# eth_lan8742a_phy.net
KiCad netlist of a schematic drawn in Altium Designer
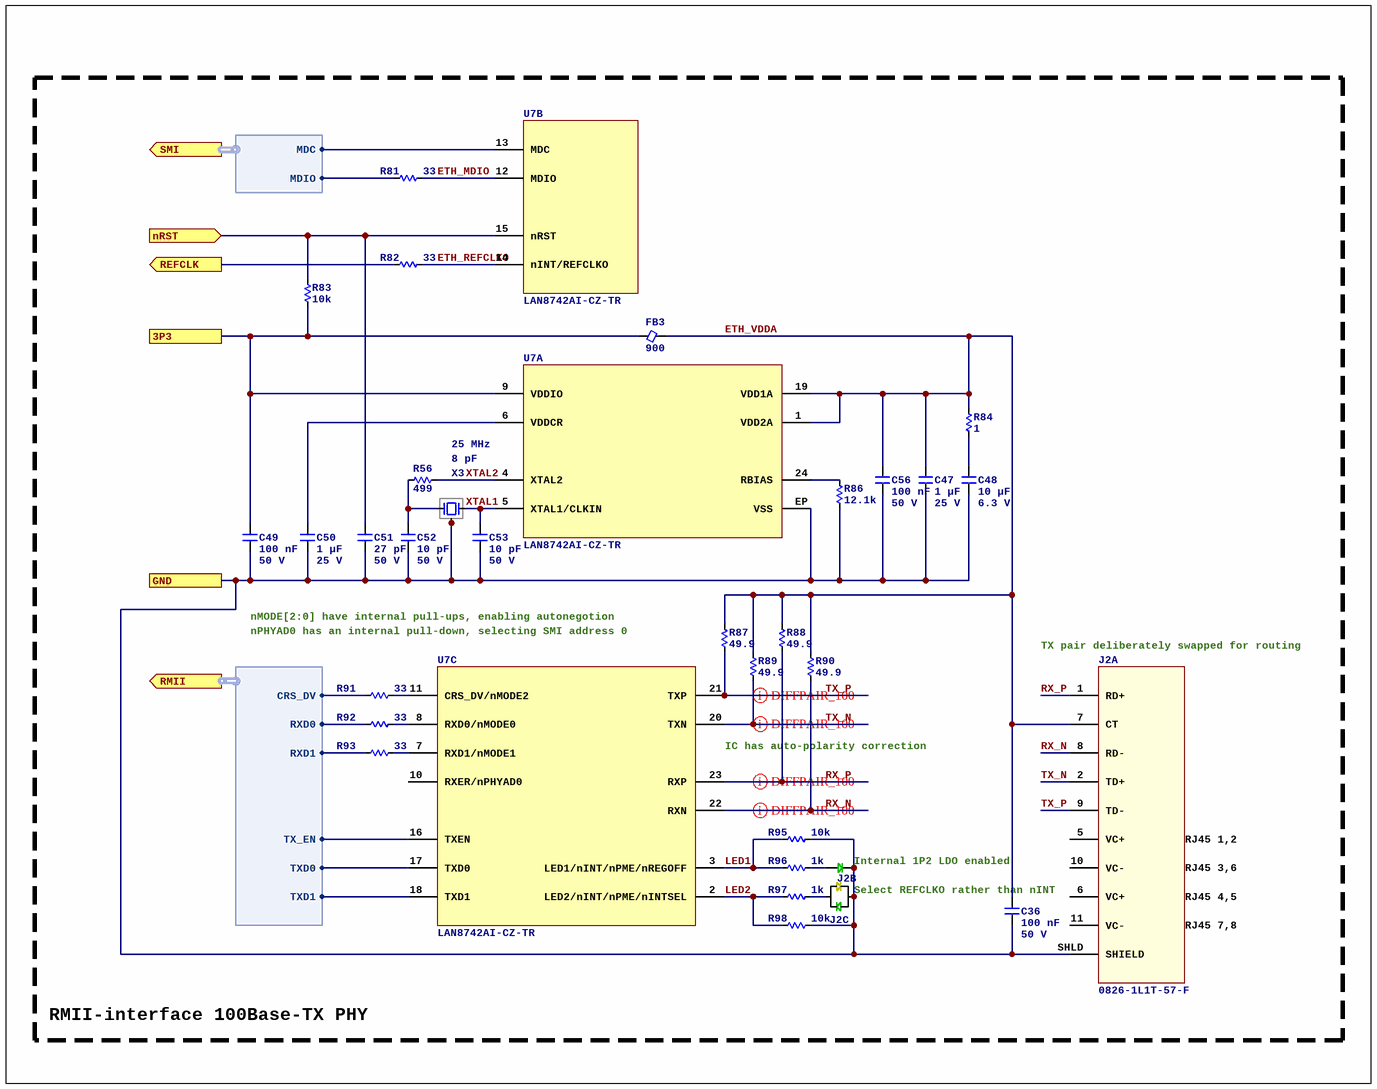
[diagram p0: eth_lan8742a_phy.SchDoc]

(export (version "E")
  (design (tool "Eeschema 10.0.6"))
  (components
    (comp (ref "C36")
      (value "CL05B104KB54PNC")
      (footprint "C0402")
      (fields
        (field (name "CAPACITANCE") "100 nF")
        (field (name "MANUFACTURER") "Samsung Electro-Mechanics")
        (field (name "VOLTAGE RATING") "50 V")
      )
      (libsource (lib "database") (part "__template_cap"))
    )
    (comp (ref "C47")
      (value "CL10B105KA8NNNC")
      (footprint "C0603")
      (fields
        (field (name "CAPACITANCE") "1 µF")
        (field (name "MANUFACTURER") "Samsung Electro-Mechanics")
        (field (name "VOLTAGE RATING") "25 V")
      )
      (libsource (lib "database") (part "__template_cap"))
    )
    (comp (ref "C48")
      (value "CC0805KKX7R5BB106")
      (footprint "C0805")
      (fields
        (field (name "CAPACITANCE") "10 µF")
        (field (name "MANUFACTURER") "YAGEO")
        (field (name "VOLTAGE RATING") "6.3 V")
      )
      (libsource (lib "database") (part "__template_cap"))
    )
    (comp (ref "C49")
      (value "CL05B104KB54PNC")
      (footprint "C0402")
      (fields
        (field (name "CAPACITANCE") "100 nF")
        (field (name "MANUFACTURER") "Samsung Electro-Mechanics")
        (field (name "VOLTAGE RATING") "50 V")
      )
      (libsource (lib "database") (part "__template_cap"))
    )
    (comp (ref "C50")
      (value "CL10B105KA8NNNC")
      (footprint "C0603")
      (fields
        (field (name "CAPACITANCE") "1 µF")
        (field (name "MANUFACTURER") "Samsung Electro-Mechanics")
        (field (name "VOLTAGE RATING") "25 V")
      )
      (libsource (lib "database") (part "__template_cap"))
    )
    (comp (ref "C51")
      (value "CC0402JRNPO9BN270")
      (footprint "C0402")
      (fields
        (field (name "CAPACITANCE") "27 pF")
        (field (name "MANUFACTURER") "YAGEO")
        (field (name "VOLTAGE RATING") "50 V")
      )
      (libsource (lib "database") (part "__template_cap"))
    )
    (comp (ref "C52")
      (value "CL05C100JB5NNNC")
      (footprint "C0402")
      (fields
        (field (name "CAPACITANCE") "10 pF")
        (field (name "MANUFACTURER") "Samsung Electro-Mechanics")
        (field (name "VOLTAGE RATING") "50 V")
      )
      (libsource (lib "database") (part "__template_cap"))
    )
    (comp (ref "C53")
      (value "CL05C100JB5NNNC")
      (footprint "C0402")
      (fields
        (field (name "CAPACITANCE") "10 pF")
        (field (name "MANUFACTURER") "Samsung Electro-Mechanics")
        (field (name "VOLTAGE RATING") "50 V")
      )
      (libsource (lib "database") (part "__template_cap"))
    )
    (comp (ref "C56")
      (value "CL05B104KB54PNC")
      (footprint "C0402")
      (fields
        (field (name "CAPACITANCE") "100 nF")
        (field (name "MANUFACTURER") "Samsung Electro-Mechanics")
        (field (name "VOLTAGE RATING") "50 V")
      )
      (libsource (lib "database") (part "__template_cap"))
    )
    (comp (ref "FB3")
      (value "BLM15PX601SN1D")
      (footprint "FB0402")
      (fields (field (name "MANUFACTURER") "Murata Electronics") (field (name "CURRENT RATING (MA)") "900"))
      (libsource (lib "database") (part "__template_fb"))
    )
    (comp (ref "J2")
      (value "0826-1L1T-57-F")
      (footprint "BELFUSE_0826-1L1T-57-F")
      (description "CONN MAGJACK 1PORT 100 BASE-T")
      (fields (field (name "MANUFACTURER") "Bel Fuse Inc"))
      (libsource (lib "") (part "0826-1L1T-57-F_2"))
    )
    (comp (ref "R56")
      (value "499")
      (footprint "R0402")
      (fields
        (field (name "TOLERANCE") "1%")
        (field (name "MANUFACTURER PART NUMBER") "0402WGF4990TCE")
        (field (name "MANUFACTURER") "UNI-ROYAL(Uniroyal Elec)")
      )
      (libsource (lib "database") (part "__template_resistor"))
    )
    (comp (ref "R81")
      (value "33")
      (footprint "R0402")
      (fields
        (field (name "TOLERANCE") "1%")
        (field (name "MANUFACTURER PART NUMBER") "CRCW040233R0FKED")
        (field (name "MANUFACTURER") "Vishay Intertech")
      )
      (libsource (lib "database") (part "__template_resistor"))
    )
    (comp (ref "R82")
      (value "33")
      (footprint "R0402")
      (fields
        (field (name "TOLERANCE") "1%")
        (field (name "MANUFACTURER PART NUMBER") "CRCW040233R0FKED")
        (field (name "MANUFACTURER") "Vishay Intertech")
      )
      (libsource (lib "database") (part "__template_resistor"))
    )
    (comp (ref "R83")
      (value "10k")
      (footprint "R0402")
      (fields
        (field (name "TOLERANCE") "1%")
        (field (name "MANUFACTURER PART NUMBER") "0402WGF1002TCE")
        (field (name "MANUFACTURER") "UNI-ROYAL(Uniroyal Elec)")
      )
      (libsource (lib "database") (part "__template_resistor"))
    )
    (comp (ref "R84")
      (value "1")
      (footprint "R0402")
      (fields
        (field (name "TOLERANCE") "1%")
        (field (name "MANUFACTURER PART NUMBER") "CRCW04021R00FKEDC")
        (field (name "MANUFACTURER") "Vishay Intertech")
      )
      (libsource (lib "database") (part "__template_resistor"))
    )
    (comp (ref "R86")
      (value "12.1k")
      (footprint "R0402")
      (fields
        (field (name "TOLERANCE") "1%")
        (field (name "MANUFACTURER PART NUMBER") "RC0402FR-0712K1L")
        (field (name "MANUFACTURER") "YAGEO")
      )
      (libsource (lib "database") (part "__template_resistor"))
    )
    (comp (ref "R87")
      (value "49.9")
      (footprint "R0402")
      (fields
        (field (name "TOLERANCE") "1%")
        (field (name "MANUFACTURER PART NUMBER") "0402WGF499JTCE")
        (field (name "MANUFACTURER") "UNI-ROYAL(Uniroyal Elec)")
      )
      (libsource (lib "database") (part "__template_resistor"))
    )
    (comp (ref "R88")
      (value "49.9")
      (footprint "R0402")
      (fields
        (field (name "TOLERANCE") "1%")
        (field (name "MANUFACTURER PART NUMBER") "0402WGF499JTCE")
        (field (name "MANUFACTURER") "UNI-ROYAL(Uniroyal Elec)")
      )
      (libsource (lib "database") (part "__template_resistor"))
    )
    (comp (ref "R89")
      (value "49.9")
      (footprint "R0402")
      (fields
        (field (name "TOLERANCE") "1%")
        (field (name "MANUFACTURER PART NUMBER") "0402WGF499JTCE")
        (field (name "MANUFACTURER") "UNI-ROYAL(Uniroyal Elec)")
      )
      (libsource (lib "database") (part "__template_resistor"))
    )
    (comp (ref "R90")
      (value "49.9")
      (footprint "R0402")
      (fields
        (field (name "TOLERANCE") "1%")
        (field (name "MANUFACTURER PART NUMBER") "0402WGF499JTCE")
        (field (name "MANUFACTURER") "UNI-ROYAL(Uniroyal Elec)")
      )
      (libsource (lib "database") (part "__template_resistor"))
    )
    (comp (ref "R91")
      (value "33")
      (footprint "R0402")
      (fields
        (field (name "TOLERANCE") "1%")
        (field (name "MANUFACTURER PART NUMBER") "CRCW040233R0FKED")
        (field (name "MANUFACTURER") "Vishay Intertech")
      )
      (libsource (lib "database") (part "__template_resistor"))
    )
    (comp (ref "R92")
      (value "33")
      (footprint "R0402")
      (fields
        (field (name "TOLERANCE") "1%")
        (field (name "MANUFACTURER PART NUMBER") "CRCW040233R0FKED")
        (field (name "MANUFACTURER") "Vishay Intertech")
      )
      (libsource (lib "database") (part "__template_resistor"))
    )
    (comp (ref "R93")
      (value "33")
      (footprint "R0402")
      (fields
        (field (name "TOLERANCE") "1%")
        (field (name "MANUFACTURER PART NUMBER") "CRCW040233R0FKED")
        (field (name "MANUFACTURER") "Vishay Intertech")
      )
      (libsource (lib "database") (part "__template_resistor"))
    )
    (comp (ref "R95")
      (value "10k")
      (footprint "R0402")
      (fields
        (field (name "TOLERANCE") "1%")
        (field (name "MANUFACTURER PART NUMBER") "0402WGF1002TCE")
        (field (name "MANUFACTURER") "UNI-ROYAL(Uniroyal Elec)")
      )
      (libsource (lib "database") (part "__template_resistor"))
    )
    (comp (ref "R96")
      (value "1k")
      (footprint "R0402")
      (fields
        (field (name "TOLERANCE") "1%")
        (field (name "MANUFACTURER PART NUMBER") "0402WGF1001TCE")
        (field (name "MANUFACTURER") "UNI-ROYAL(Uniroyal Elec)")
      )
      (libsource (lib "database") (part "__template_resistor"))
    )
    (comp (ref "R97")
      (value "1k")
      (footprint "R0402")
      (fields
        (field (name "TOLERANCE") "1%")
        (field (name "MANUFACTURER PART NUMBER") "0402WGF1001TCE")
        (field (name "MANUFACTURER") "UNI-ROYAL(Uniroyal Elec)")
      )
      (libsource (lib "database") (part "__template_resistor"))
    )
    (comp (ref "R98")
      (value "10k")
      (footprint "R0402")
      (fields
        (field (name "TOLERANCE") "1%")
        (field (name "MANUFACTURER PART NUMBER") "0402WGF1002TCE")
        (field (name "MANUFACTURER") "UNI-ROYAL(Uniroyal Elec)")
      )
      (libsource (lib "database") (part "__template_resistor"))
    )
    (comp (ref "U7")
      (value "LAN8742AI-CZ-TR")
      (footprint "24QFN4E")
      (description "Ethernet Transceiver, PQCC24")
      (fields (field (name "MANUFACTURER") "Microchip"))
      (libsource (lib "database") (part "LAN8742AI-CZ-TR"))
    )
    (comp (ref "X3")
      (value "ABM11W-25.0000MHZ-8-D1X-T3")
      (footprint "4_SMD_2.0X1.6MM")
      (description "25 MHz ±10ppm Crystal 8pF 50 Ohms 4-SMD, No Lead")
      (fields
        (field (name "MANUFACTURER") "Abracon LLC")
        (field (name "FREQUENCY") "25 MHz")
        (field (name "CAPACITANCE") "8 pF")
      )
      (libsource (lib "database") (part "__template_crystal_4pin"))
    )
  )
  (nets
    (net (code "3") (name "/3P3") (class "Default")
      (node (ref "C49") (pin "1") (pintype "passive"))
      (node (ref "FB3") (pin "1") (pintype "passive"))
      (node (ref "R83") (pin "1") (pintype "passive"))
      (node (ref "U7") (pin "9") (pinfunction "VDDIO_9") (pintype "passive"))
    )
    (net (code "4") (name "/CRS_DV") (class "Default") (node (ref "R91") (pin "2") (pintype "passive")))
    (net (code "5") (name "/ETH_MDIO") (class "Default")
      (node (ref "R81") (pin "1") (pintype "passive"))
      (node (ref "U7") (pin "12") (pinfunction "MDIO_12") (pintype "passive"))
    )
    (net (code "6") (name "/ETH_REFCLKO") (class "Default")
      (node (ref "R82") (pin "1") (pintype "passive"))
      (node (ref "U7") (pin "14") (pinfunction "nINT/REFCLKO_14") (pintype "passive"))
    )
    (net (code "7") (name "/ETH_VDDA") (class "Default")
      (node (ref "C36") (pin "1") (pintype "passive"))
      (node (ref "C47") (pin "1") (pintype "passive"))
      (node (ref "C56") (pin "1") (pintype "passive"))
      (node (ref "FB3") (pin "2") (pintype "passive"))
      (node (ref "J2") (pin "7") (pinfunction "CT_7") (pintype "passive"))
      (node (ref "R84") (pin "2") (pintype "passive"))
      (node (ref "R87") (pin "1") (pintype "passive"))
      (node (ref "R88") (pin "1") (pintype "passive"))
      (node (ref "R89") (pin "1") (pintype "passive"))
      (node (ref "R90") (pin "1") (pintype "passive"))
      (node (ref "U7") (pin "1") (pinfunction "VDD2A_1") (pintype "passive"))
      (node (ref "U7") (pin "19") (pinfunction "VDD1A_19") (pintype "passive"))
    )
    (net (code "8") (name "/GND") (class "Default")
      (node (ref "C36") (pin "2") (pintype "passive"))
      (node (ref "C47") (pin "2") (pintype "passive"))
      (node (ref "C48") (pin "2") (pintype "passive"))
      (node (ref "C49") (pin "2") (pintype "passive"))
      (node (ref "C50") (pin "2") (pintype "passive"))
      (node (ref "C51") (pin "2") (pintype "passive"))
      (node (ref "C52") (pin "2") (pintype "passive"))
      (node (ref "C53") (pin "2") (pintype "passive"))
      (node (ref "C56") (pin "2") (pintype "passive"))
      (node (ref "J2") (pin "13") (pintype "passive"))
      (node (ref "J2") (pin "14") (pintype "passive"))
      (node (ref "J2") (pin "SHLD") (pinfunction "SHIELD_SHLD") (pintype "passive"))
      (node (ref "R86") (pin "2") (pintype "passive"))
      (node (ref "R95") (pin "2") (pintype "passive"))
      (node (ref "R98") (pin "2") (pintype "passive"))
      (node (ref "U7") (pin "EP") (pinfunction "VSS_EP") (pintype "passive"))
      (node (ref "X3") (pin "2") (pinfunction "2_2") (pintype "passive"))
      (node (ref "X3") (pin "4") (pinfunction "4_4") (pintype "passive"))
    )
    (net (code "9") (name "/LED1") (class "Default")
      (node (ref "R95") (pin "1") (pintype "passive"))
      (node (ref "R96") (pin "2") (pintype "passive"))
      (node (ref "U7") (pin "3") (pinfunction "LED1/nINT/nPME/nREGOFF_3") (pintype "passive"))
    )
    (net (code "10") (name "/LED2") (class "Default")
      (node (ref "R97") (pin "2") (pintype "passive"))
      (node (ref "R98") (pin "1") (pintype "passive"))
      (node (ref "U7") (pin "2") (pinfunction "LED2/nINT/nPME/nINTSEL_2") (pintype "passive"))
    )
    (net (code "11") (name "/MDC") (class "Default")
      (node (ref "U7") (pin "13") (pinfunction "MDC_13") (pintype "passive"))
    )
    (net (code "12") (name "/MDIO") (class "Default") (node (ref "R81") (pin "2") (pintype "passive")))
    (net (code "13") (name "/REFCLK") (class "Default") (node (ref "R82") (pin "2") (pintype "passive")))
    (net (code "14") (name "/RXD0") (class "Default") (node (ref "R92") (pin "2") (pintype "passive")))
    (net (code "15") (name "/RXD1") (class "Default") (node (ref "R93") (pin "2") (pintype "passive")))
    (net (code "16") (name "/RX_N") (class "Default")
      (node (ref "J2") (pin "8") (pinfunction "RD-_8") (pintype "passive"))
      (node (ref "R90") (pin "2") (pintype "passive"))
      (node (ref "U7") (pin "22") (pinfunction "RXN_22") (pintype "passive"))
    )
    (net (code "17") (name "/RX_P") (class "Default")
      (node (ref "J2") (pin "1") (pinfunction "RD+_1") (pintype "passive"))
      (node (ref "R88") (pin "2") (pintype "passive"))
      (node (ref "U7") (pin "23") (pinfunction "RXP_23") (pintype "passive"))
    )
    (net (code "18") (name "/TXD0") (class "Default")
      (node (ref "U7") (pin "17") (pinfunction "TXD0_17") (pintype "passive"))
    )
    (net (code "19") (name "/TXD1") (class "Default")
      (node (ref "U7") (pin "18") (pinfunction "TXD1_18") (pintype "passive"))
    )
    (net (code "20") (name "/TX_EN") (class "Default")
      (node (ref "U7") (pin "16") (pinfunction "TXEN_16") (pintype "passive"))
    )
    (net (code "21") (name "/TX_N") (class "Default")
      (node (ref "J2") (pin "2") (pinfunction "TD+_2") (pintype "passive"))
      (node (ref "R89") (pin "2") (pintype "passive"))
      (node (ref "U7") (pin "20") (pinfunction "TXN_20") (pintype "passive"))
    )
    (net (code "22") (name "/TX_P") (class "Default")
      (node (ref "J2") (pin "9") (pinfunction "TD-_9") (pintype "passive"))
      (node (ref "R87") (pin "2") (pintype "passive"))
      (node (ref "U7") (pin "21") (pinfunction "TXP_21") (pintype "passive"))
    )
    (net (code "23") (name "/XTAL1") (class "Default")
      (node (ref "C53") (pin "1") (pintype "passive"))
      (node (ref "U7") (pin "5") (pinfunction "XTAL1/CLKIN_5") (pintype "passive"))
      (node (ref "X3") (pin "3") (pinfunction "3_3") (pintype "passive"))
    )
    (net (code "24") (name "/XTAL2") (class "Default")
      (node (ref "R56") (pin "1") (pintype "passive"))
      (node (ref "U7") (pin "4") (pinfunction "XTAL2_4") (pintype "passive"))
    )
    (net (code "25") (name "/nRST") (class "Default")
      (node (ref "C51") (pin "1") (pintype "passive"))
      (node (ref "R83") (pin "2") (pintype "passive"))
      (node (ref "U7") (pin "15") (pinfunction "nRST_15") (pintype "passive"))
    )
    (net (code "28") (name "Net-(C48-Pad1)") (class "Default")
      (node (ref "C48") (pin "1") (pintype "passive"))
      (node (ref "R84") (pin "1") (pintype "passive"))
    )
    (net (code "29") (name "Net-(C52-Pad1)") (class "Default")
      (node (ref "C52") (pin "1") (pintype "passive"))
      (node (ref "R56") (pin "2") (pintype "passive"))
      (node (ref "X3") (pin "1") (pinfunction "1_1") (pintype "passive"))
    )
    (net (code "30") (name "Net-(J2-Pad12)") (class "Default")
      (node (ref "J2") (pin "12") (pintype "passive"))
      (node (ref "R97") (pin "1") (pintype "passive"))
    )
    (net (code "31") (name "Net-(J2-Pad15)") (class "Default")
      (node (ref "J2") (pin "15") (pintype "passive"))
      (node (ref "R96") (pin "1") (pintype "passive"))
    )
    (net (code "32") (name "Net-(U7A-RBIAS)") (class "Default")
      (node (ref "R86") (pin "1") (pintype "passive"))
      (node (ref "U7") (pin "24") (pinfunction "RBIAS_24") (pintype "passive"))
    )
    (net (code "33") (name "Net-(U7A-VDDCR)") (class "Default")
      (node (ref "C50") (pin "1") (pintype "passive"))
      (node (ref "U7") (pin "6") (pinfunction "VDDCR_6") (pintype "passive"))
    )
    (net (code "34") (name "Net-(U7C-CRS_DV{slash}nMODE2)") (class "Default")
      (node (ref "R91") (pin "1") (pintype "passive"))
      (node (ref "U7") (pin "11") (pinfunction "CRS_DV/nMODE2_11") (pintype "passive"))
    )
    (net (code "35") (name "Net-(U7C-RXD0{slash}nMODE0)") (class "Default")
      (node (ref "R92") (pin "1") (pintype "passive"))
      (node (ref "U7") (pin "8") (pinfunction "RXD0/nMODE0_8") (pintype "passive"))
    )
    (net (code "36") (name "Net-(U7C-RXD1{slash}nMODE1)") (class "Default")
      (node (ref "R93") (pin "1") (pintype "passive"))
      (node (ref "U7") (pin "7") (pinfunction "RXD1/nMODE1_7") (pintype "passive"))
    )
    (net (code "37") (name "unconnected-(J2A-VC+-Pad5)") (class "Default")
      (node (ref "J2") (pin "5") (pinfunction "VC+_5") (pintype "passive"))
    )
    (net (code "38") (name "unconnected-(J2A-VC+-Pad6)") (class "Default")
      (node (ref "J2") (pin "6") (pinfunction "VC+_6") (pintype "passive"))
    )
    (net (code "39") (name "unconnected-(J2A-VC--Pad10)") (class "Default")
      (node (ref "J2") (pin "10") (pinfunction "VC-_10") (pintype "passive"))
    )
    (net (code "40") (name "unconnected-(J2A-VC--Pad11)") (class "Default")
      (node (ref "J2") (pin "11") (pinfunction "VC-_11") (pintype "passive"))
    )
    (net (code "41") (name "unconnected-(U7C-RXER{slash}nPHYAD0-Pad10)") (class "Default")
      (node (ref "U7") (pin "10") (pinfunction "RXER/nPHYAD0_10") (pintype "passive"))
    )
  )
)
